# ES_Daisy_Pod_Rev5.net
KiCad netlist of a schematic drawn in EAGLE
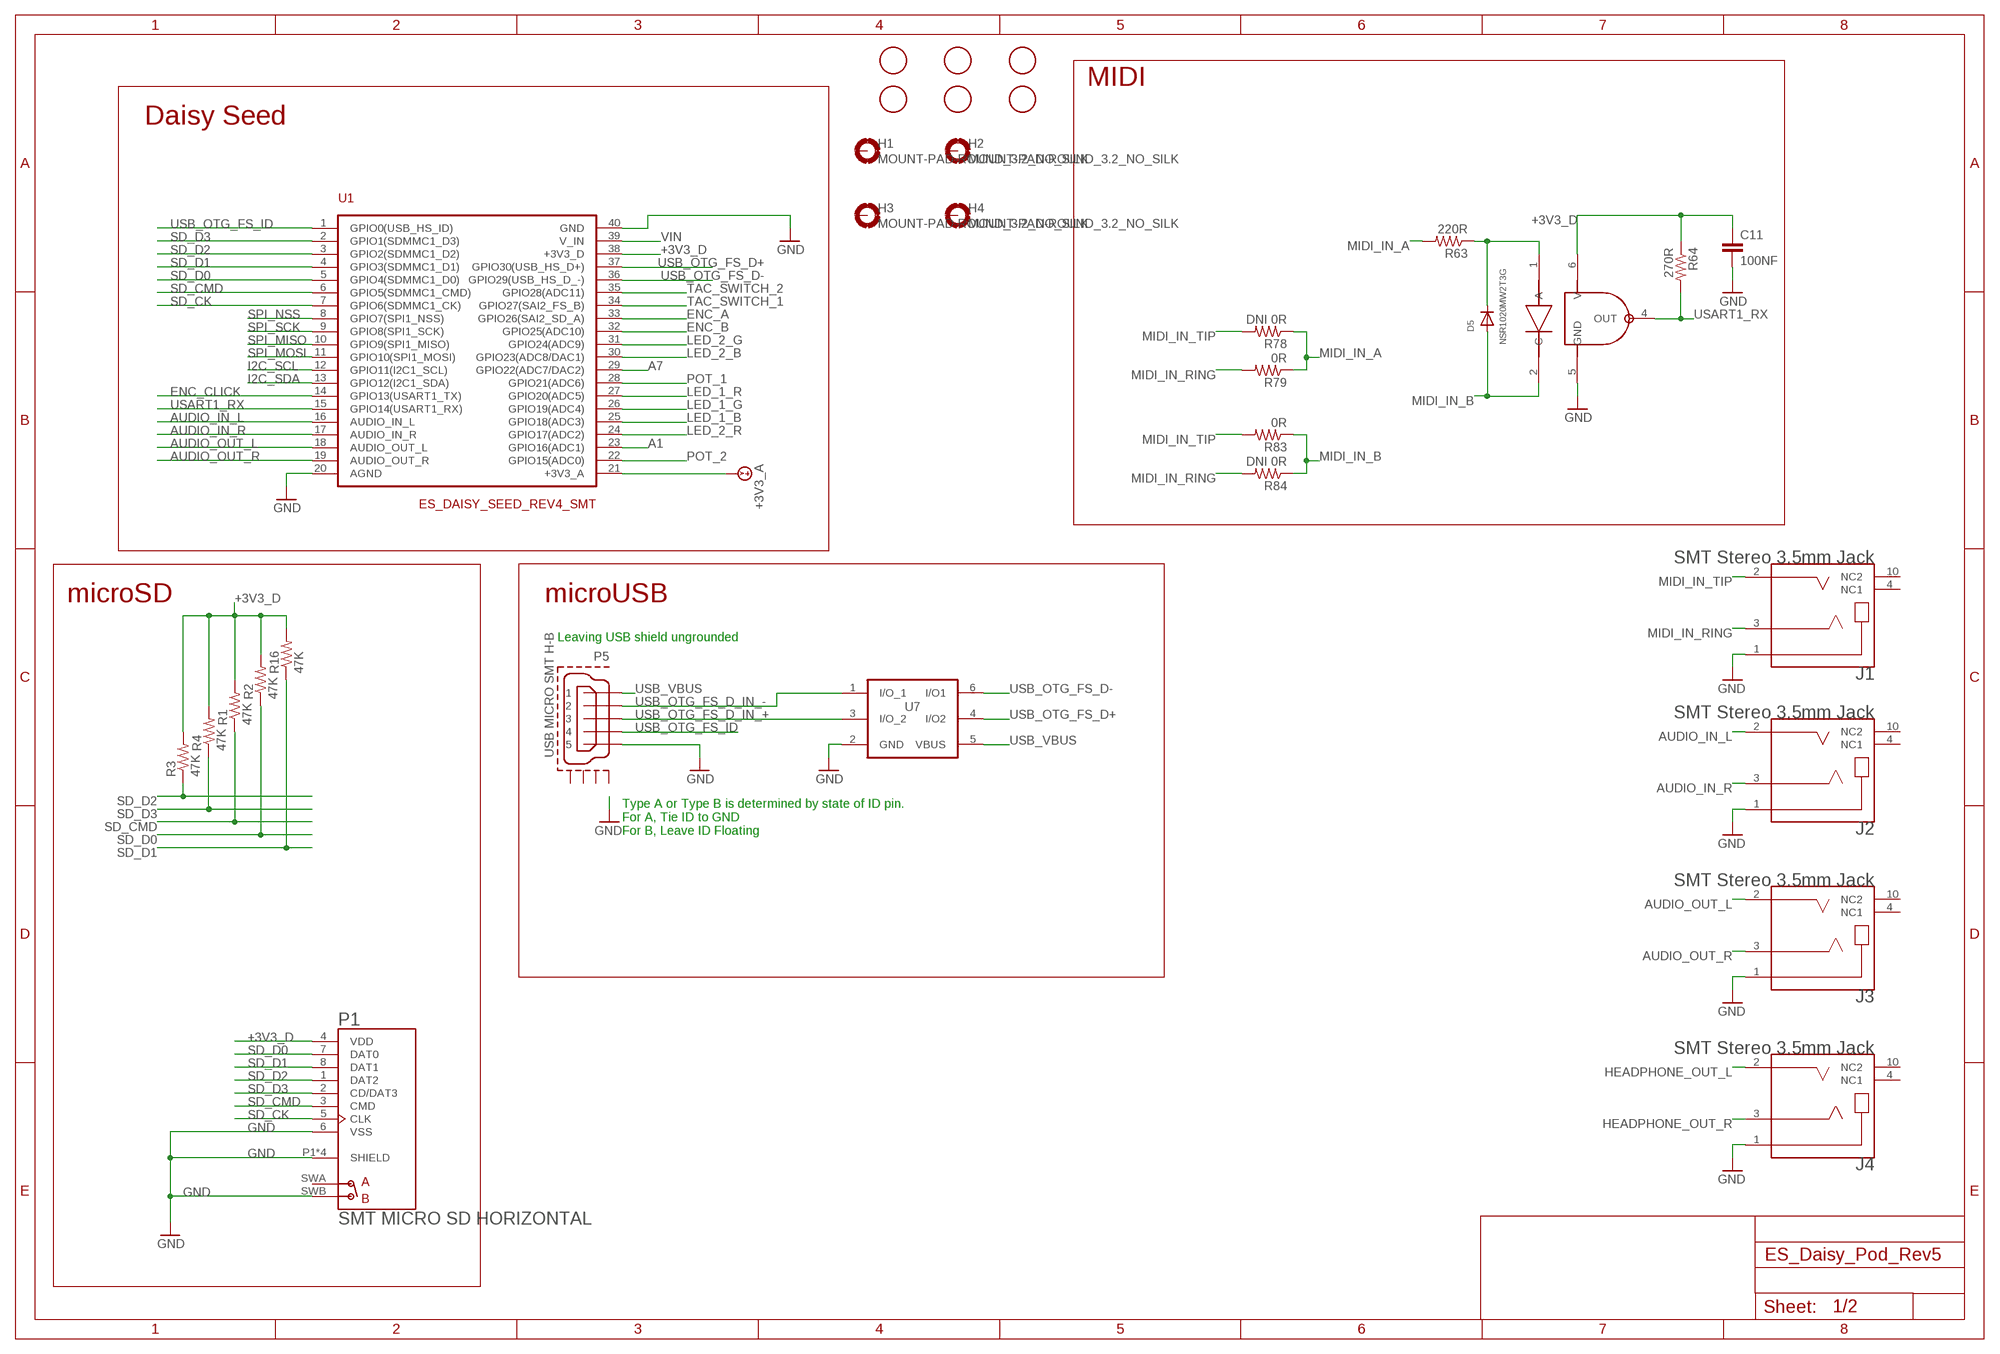
[diagram p0: schematic, sheet 1]
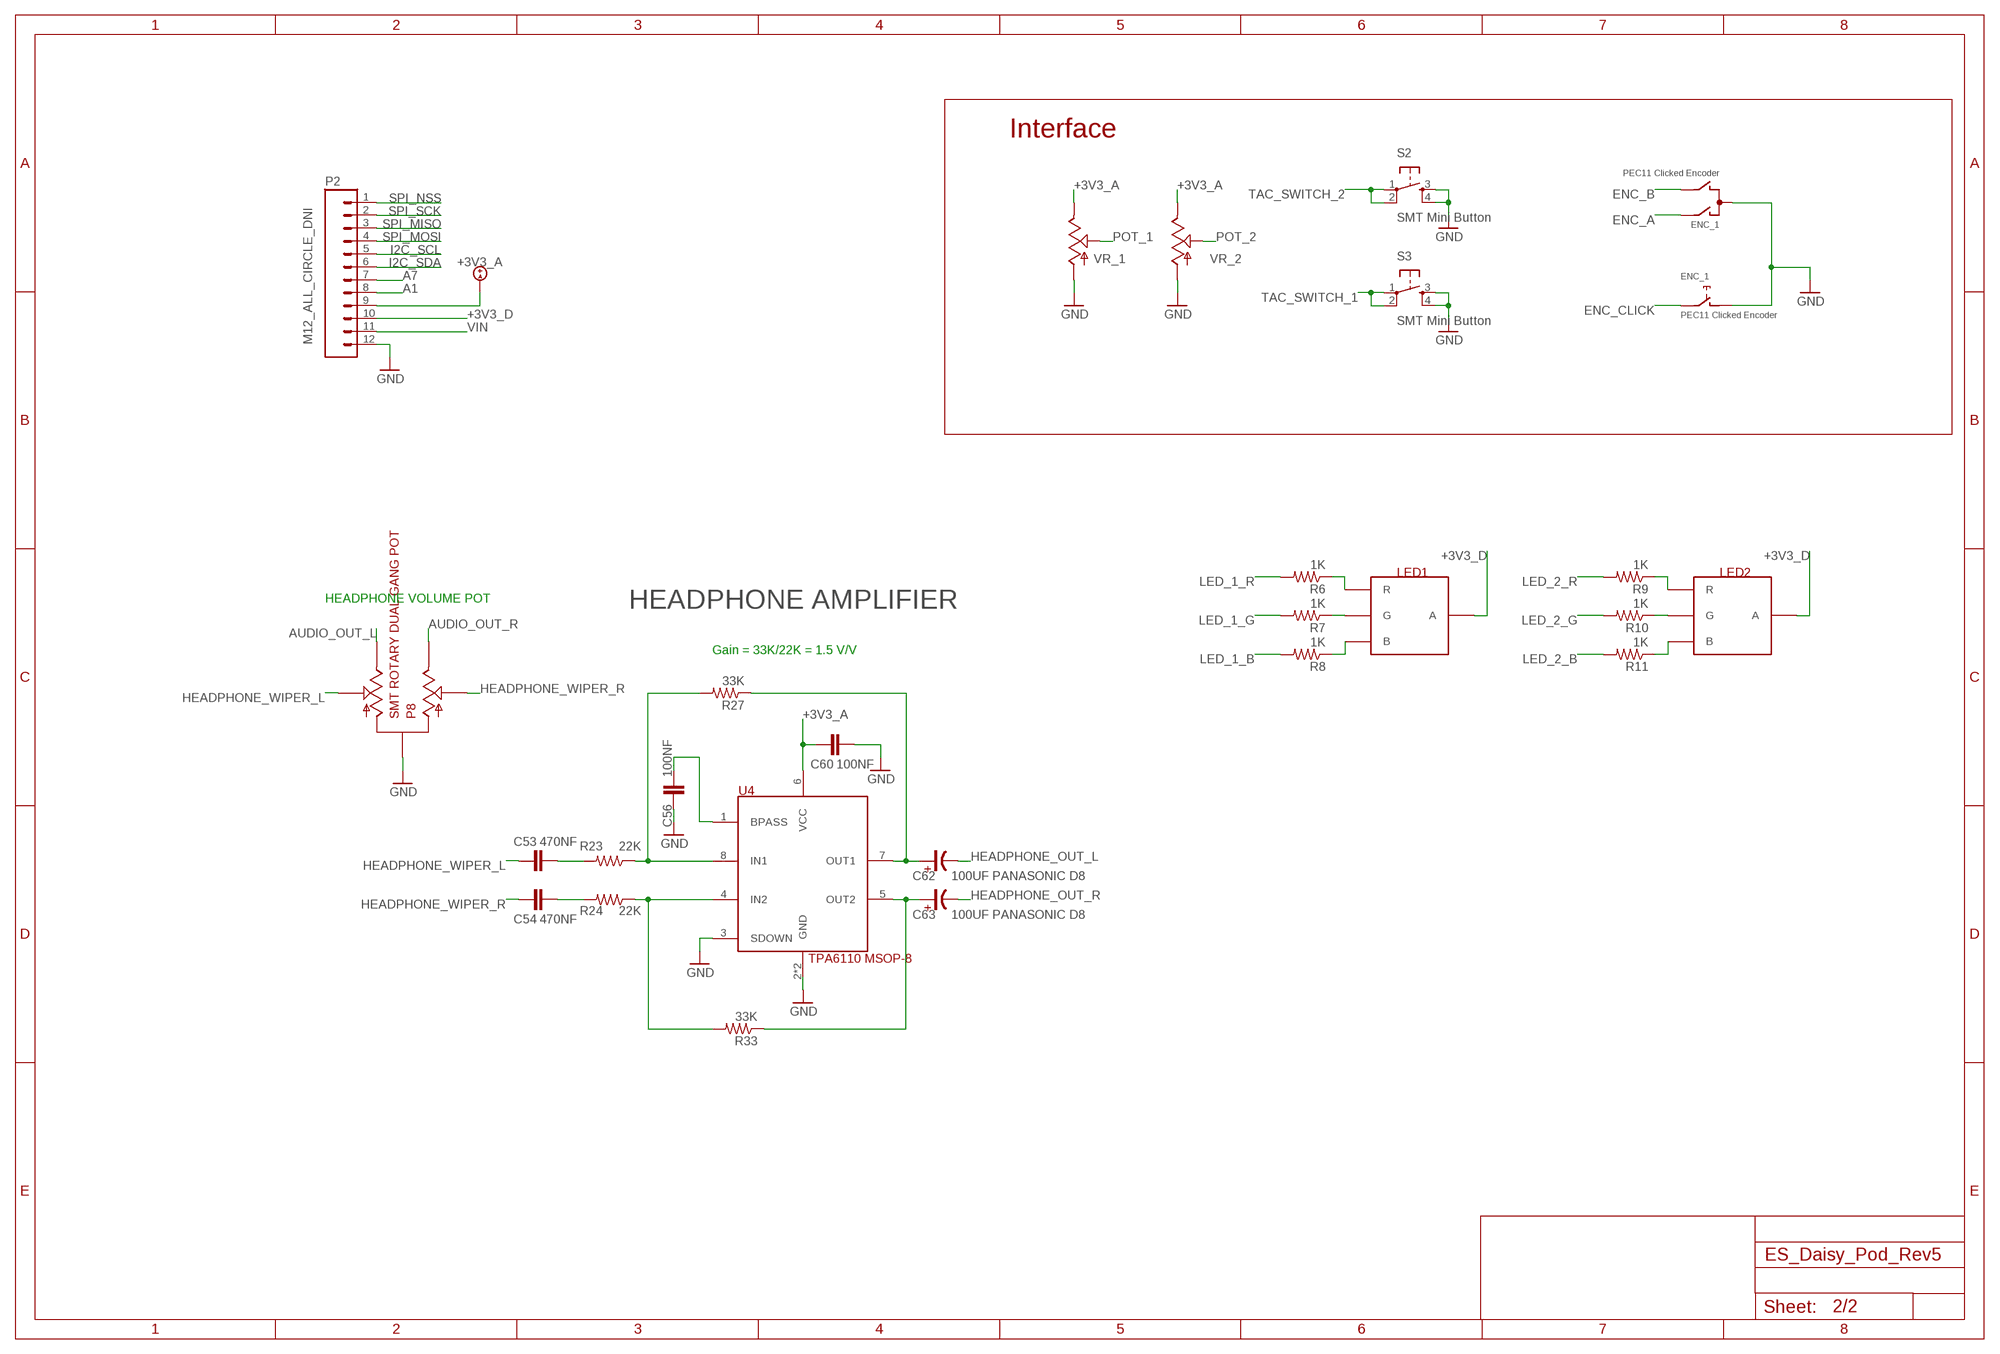
[diagram p1: schematic, sheet 2]

(export (version "E")
  (design (tool "Eeschema 10.0.6"))
  (components
    (comp (ref "C53")
      (value "470NF")
      (footprint "eagle-import:C0603")
      (libsource (lib "eagle-import") (part "C-EUC0603"))
    )
    (comp (ref "C54")
      (value "470NF")
      (footprint "eagle-import:C0603")
      (libsource (lib "eagle-import") (part "C-EUC0603"))
    )
    (comp (ref "C56")
      (value "100NF")
      (footprint "eagle-import:C0402")
      (libsource (lib "eagle-import") (part "C-EUC0402"))
    )
    (comp (ref "C60")
      (value "100NF")
      (footprint "eagle-import:C0402")
      (libsource (lib "eagle-import") (part "C-EUC0402"))
    )
    (comp (ref "C62")
      (value "100UF PANASONIC D8")
      (footprint "eagle-import:PANASONIC_D")
      (libsource (lib "eagle-import") (part "C-EU-POL_D"))
    )
    (comp (ref "C63")
      (value "100UF PANASONIC D8")
      (footprint "eagle-import:PANASONIC_D")
      (libsource (lib "eagle-import") (part "C-EU-POL_D"))
    )
    (comp (ref "ENC_1")
      (value "PEC11 Clicked Encoder")
      (footprint "eagle-import:VH1-147")
      (libsource (lib "eagle-import") (part "ENCODER_SMT"))
    )
    (comp (ref "LED1")
      (value "RGB LED SMT PLCC4")
      (footprint "eagle-import:P-LCC-4-3")
      (fields (field (name "MPN") "CLVBA-FKA-CC1F1L1BB7R3R3"))
      (libsource (lib "eagle-import") (part "LED_RGB_SMT"))
    )
    (comp (ref "LED2")
      (value "RGB LED SMT PLCC4")
      (footprint "eagle-import:P-LCC-4-3")
      (fields (field (name "MPN") "CLVBA-FKA-CC1F1L1BB7R3R3"))
      (libsource (lib "eagle-import") (part "LED_RGB_SMT"))
    )
    (comp (ref "P2")
      (value "M12_ALL_CIRCLE_DNI")
      (footprint "eagle-import:1X12_NO_SILK_ALL_CIRCLE")
      (libsource (lib "eagle-import") (part "M12_ALL_CIRCLE"))
    )
    (comp (ref "P8")
      (value "SMT ROTARY DUAL GANG POT")
      (footprint "eagle-import:RK10J12R0A0B")
      (libsource (lib "eagle-import") (part "ROTARY_POT"))
    )
    (comp (ref "R6")
      (value "1K")
      (footprint "eagle-import:R0402")
      (libsource (lib "eagle-import") (part "R-US_R0402"))
    )
    (comp (ref "R7")
      (value "1K")
      (footprint "eagle-import:R0402")
      (libsource (lib "eagle-import") (part "R-US_R0402"))
    )
    (comp (ref "R8")
      (value "1K")
      (footprint "eagle-import:R0402")
      (libsource (lib "eagle-import") (part "R-US_R0402"))
    )
    (comp (ref "R9")
      (value "1K")
      (footprint "eagle-import:R0402")
      (libsource (lib "eagle-import") (part "R-US_R0402"))
    )
    (comp (ref "R10")
      (value "1K")
      (footprint "eagle-import:R0402")
      (libsource (lib "eagle-import") (part "R-US_R0402"))
    )
    (comp (ref "R11")
      (value "1K")
      (footprint "eagle-import:R0402")
      (libsource (lib "eagle-import") (part "R-US_R0402"))
    )
    (comp (ref "R23")
      (value "22K")
      (footprint "eagle-import:R0603")
      (libsource (lib "eagle-import") (part "R-US_R0603"))
    )
    (comp (ref "R24")
      (value "22K")
      (footprint "eagle-import:R0603")
      (libsource (lib "eagle-import") (part "R-US_R0603"))
    )
    (comp (ref "R27")
      (value "33K")
      (footprint "eagle-import:R0603")
      (libsource (lib "eagle-import") (part "R-US_R0603"))
    )
    (comp (ref "R33")
      (value "33K")
      (footprint "eagle-import:R0603")
      (libsource (lib "eagle-import") (part "R-US_R0603"))
    )
    (comp (ref "S2")
      (value "SMT Mini Button")
      (footprint "eagle-import:TL3301SPF160QJ")
      (fields (field (name "MPN") "TL3301SPF160QJ"))
      (libsource (lib "eagle-import") (part "TAC_SWITCH_SMT"))
    )
    (comp (ref "S3")
      (value "SMT Mini Button")
      (footprint "eagle-import:TL3301SPF160QJ")
      (fields (field (name "MPN") "TL3301SPF160QJ"))
      (libsource (lib "eagle-import") (part "TAC_SWITCH_SMT"))
    )
    (comp (ref "U4")
      (value "TPA6110 MSOP-8")
      (footprint "eagle-import:MSOP_8_PWRPAD")
      (libsource (lib "eagle-import") (part "TPA6110MSOP"))
    )
    (comp (ref "VR_1")
      (value "P-10K-B-R-PIP")
      (footprint "eagle-import:9MM_SNAP-IN_POT_SILK_PIP")
      (libsource (lib "eagle-import") (part "POT_9MM_SNAP-IN__SILK_PIP"))
    )
    (comp (ref "VR_2")
      (value "P-10K-B-R-PIP")
      (footprint "eagle-import:9MM_SNAP-IN_POT_SILK_PIP")
      (libsource (lib "eagle-import") (part "POT_9MM_SNAP-IN__SILK_PIP"))
    )
    (comp (ref "C11")
      (value "100NF")
      (footprint "eagle-import:C0402")
      (libsource (lib "eagle-import") (part "C-EUC0402"))
    )
    (comp (ref "D5")
      (value "NSR1020MW2T3G")
      (footprint "eagle-import:SOD-323F")
      (libsource (lib "eagle-import") (part "DIODE_SOD-323F"))
    )
    (comp (ref "FD1")
      (value "FIDUCIAL")
      (footprint "eagle-import:FIDUCIAL_1MM")
      (libsource (lib "eagle-import") (part "FIDUCIAL"))
    )
    (comp (ref "FD2")
      (value "FIDUCIAL")
      (footprint "eagle-import:FIDUCIAL_1MM")
      (libsource (lib "eagle-import") (part "FIDUCIAL"))
    )
    (comp (ref "FD3")
      (value "FIDUCIAL")
      (footprint "eagle-import:FIDUCIAL_1MM")
      (libsource (lib "eagle-import") (part "FIDUCIAL"))
    )
    (comp (ref "FD4")
      (value "FIDUCIAL")
      (footprint "eagle-import:FIDUCIAL_1MM")
      (libsource (lib "eagle-import") (part "FIDUCIAL"))
    )
    (comp (ref "FD5")
      (value "FIDUCIAL")
      (footprint "eagle-import:FIDUCIAL_1MM")
      (libsource (lib "eagle-import") (part "FIDUCIAL"))
    )
    (comp (ref "FD6")
      (value "FIDUCIAL")
      (footprint "eagle-import:FIDUCIAL_1MM")
      (libsource (lib "eagle-import") (part "FIDUCIAL"))
    )
    (comp (ref "H1")
      (value "MOUNT-PAD-ROUND_3.2_NO_SILK")
      (footprint "eagle-import:32-PAD_NO_SILK")
      (libsource (lib "eagle-import") (part "MOUNT-PAD-ROUND_3.2_NO_SILK"))
    )
    (comp (ref "H2")
      (value "MOUNT-PAD-ROUND_3.2_NO_SILK")
      (footprint "eagle-import:32-PAD_NO_SILK")
      (libsource (lib "eagle-import") (part "MOUNT-PAD-ROUND_3.2_NO_SILK"))
    )
    (comp (ref "H3")
      (value "MOUNT-PAD-ROUND_3.2_NO_SILK")
      (footprint "eagle-import:32-PAD_NO_SILK")
      (libsource (lib "eagle-import") (part "MOUNT-PAD-ROUND_3.2_NO_SILK"))
    )
    (comp (ref "H4")
      (value "MOUNT-PAD-ROUND_3.2_NO_SILK")
      (footprint "eagle-import:32-PAD_NO_SILK")
      (libsource (lib "eagle-import") (part "MOUNT-PAD-ROUND_3.2_NO_SILK"))
    )
    (comp (ref "J1")
      (value "SMT Stereo 3.5mm Jack")
      (footprint "eagle-import:CUI_SJ2-35863B1-SMT-TR")
      (fields (field (name "MF") "CUI Inc.") (field (name "MP") "SJ2-35863B1-SMT-TR"))
      (libsource (lib "eagle-import") (part "SJ2_TRS_JACK"))
    )
    (comp (ref "J2")
      (value "SMT Stereo 3.5mm Jack")
      (footprint "eagle-import:CUI_SJ2-35863B1-SMT-TR")
      (fields (field (name "MF") "CUI Inc.") (field (name "MP") "SJ2-35863B1-SMT-TR"))
      (libsource (lib "eagle-import") (part "SJ2_TRS_JACK"))
    )
    (comp (ref "J3")
      (value "SMT Stereo 3.5mm Jack")
      (footprint "eagle-import:CUI_SJ2-35863B1-SMT-TR")
      (fields (field (name "MF") "CUI Inc.") (field (name "MP") "SJ2-35863B1-SMT-TR"))
      (libsource (lib "eagle-import") (part "SJ2_TRS_JACK"))
    )
    (comp (ref "J4")
      (value "SMT Stereo 3.5mm Jack")
      (footprint "eagle-import:CUI_SJ2-35863B1-SMT-TR")
      (fields (field (name "MF") "CUI Inc.") (field (name "MP") "SJ2-35863B1-SMT-TR"))
      (libsource (lib "eagle-import") (part "SJ2_TRS_JACK"))
    )
    (comp (ref "P1")
      (value "SMT MICRO SD HORIZONTAL")
      (footprint "eagle-import:HRS_DM3AT-SF-PEJM5")
      (fields (field (name "MF") "Hirose") (field (name "MP") "DM3AT-SF-PEJM5"))
      (libsource (lib "eagle-import") (part "MICRO_SD_RIGHT_ANGLE"))
    )
    (comp (ref "P5")
      (value "USB MICRO SMT H-B")
      (footprint "eagle-import:47589-0001_CUT2")
      (libsource (lib "eagle-import") (part "USB_MICRO_AB_CUT2"))
    )
    (comp (ref "R1")
      (value "47K")
      (footprint "eagle-import:R0603")
      (libsource (lib "eagle-import") (part "R-US_R0603"))
    )
    (comp (ref "R2")
      (value "47K")
      (footprint "eagle-import:R0603")
      (libsource (lib "eagle-import") (part "R-US_R0603"))
    )
    (comp (ref "R3")
      (value "47K")
      (footprint "eagle-import:R0603")
      (libsource (lib "eagle-import") (part "R-US_R0603"))
    )
    (comp (ref "R4")
      (value "47K")
      (footprint "eagle-import:R0603")
      (libsource (lib "eagle-import") (part "R-US_R0603"))
    )
    (comp (ref "R16")
      (value "47K")
      (footprint "eagle-import:R0603")
      (libsource (lib "eagle-import") (part "R-US_R0603"))
    )
    (comp (ref "R63")
      (value "220R")
      (footprint "eagle-import:R0603")
      (libsource (lib "eagle-import") (part "R-US_R0603"))
    )
    (comp (ref "R64")
      (value "270R")
      (footprint "eagle-import:R0603")
      (libsource (lib "eagle-import") (part "R-US_R0603"))
    )
    (comp (ref "R78")
      (value "DNI 0R")
      (footprint "eagle-import:R0603")
      (libsource (lib "eagle-import") (part "R-US_R0603"))
    )
    (comp (ref "R79")
      (value "0R")
      (footprint "eagle-import:R0603")
      (libsource (lib "eagle-import") (part "R-US_R0603"))
    )
    (comp (ref "R83")
      (value "0R")
      (footprint "eagle-import:R0603")
      (libsource (lib "eagle-import") (part "R-US_R0603"))
    )
    (comp (ref "R84")
      (value "DNI 0R")
      (footprint "eagle-import:R0603")
      (libsource (lib "eagle-import") (part "R-US_R0603"))
    )
    (comp (ref "U1")
      (value "ES_DAISY_SEED_REV4_SMT")
      (footprint "eagle-import:ES_DAISY_SEED_SMT")
      (libsource (lib "eagle-import") (part "ES_DAISY_SEED_REV4_SMT"))
    )
    (comp (ref "U7")
      (value "USBLC6 TVS SOT-23-6")
      (footprint "eagle-import:SOT-23-6L")
      (fields (field (name "MPN") "USBLC6-2SC6"))
      (libsource (lib "eagle-import") (part "USBLC6-2SC6"))
    )
    (comp (ref "U15")
      (value "H11L1SR2M")
      (footprint "eagle-import:DIL06_GULLWING")
      (libsource (lib "eagle-import") (part "OPTOISOLATOR_H11L1M"))
    )
  )
  (nets
    (net (code "1") (name "+3V3_A") (class "Default")
      (node (ref "C60") (pin "2") (pinfunction "2_2") (pintype "passive"))
      (node (ref "P2") (pin "9") (pinfunction "9_9") (pintype "passive"))
      (node (ref "U1") (pin "21") (pinfunction "+3V3_A_21") (pintype "bidirectional"))
      (node (ref "U4") (pin "6") (pinfunction "VCC_6") (pintype "bidirectional"))
      (node (ref "VR_1") (pin "3") (pinfunction "3_3") (pintype "passive"))
      (node (ref "VR_2") (pin "3") (pinfunction "3_3") (pintype "passive"))
    )
    (net (code "2") (name "+3V3_D") (class "Default")
      (node (ref "C11") (pin "1") (pinfunction "1_1") (pintype "passive"))
      (node (ref "LED1") (pin "2") (pinfunction "A_2") (pintype "bidirectional"))
      (node (ref "LED2") (pin "2") (pinfunction "A_2") (pintype "bidirectional"))
      (node (ref "P1") (pin "4") (pinfunction "VDD_4") (pintype "power_in"))
      (node (ref "P2") (pin "10") (pinfunction "10_10") (pintype "passive"))
      (node (ref "R1") (pin "2") (pinfunction "2_2") (pintype "passive"))
      (node (ref "R16") (pin "2") (pinfunction "2_2") (pintype "passive"))
      (node (ref "R2") (pin "2") (pinfunction "2_2") (pintype "passive"))
      (node (ref "R3") (pin "2") (pinfunction "2_2") (pintype "passive"))
      (node (ref "R4") (pin "2") (pinfunction "2_2") (pintype "passive"))
      (node (ref "R64") (pin "1") (pinfunction "1_1") (pintype "passive"))
      (node (ref "U1") (pin "38") (pinfunction "+3V3_D_38") (pintype "bidirectional"))
      (node (ref "U15") (pin "6") (pinfunction "V_6") (pintype "bidirectional"))
    )
    (net (code "3") (name "A1") (class "Default")
      (node (ref "P2") (pin "8") (pinfunction "8_8") (pintype "passive"))
      (node (ref "U1") (pin "23") (pinfunction "GPIO16(ADC1)_23") (pintype "bidirectional"))
    )
    (net (code "4") (name "A7") (class "Default")
      (node (ref "P2") (pin "7") (pinfunction "7_7") (pintype "passive"))
      (node (ref "U1") (pin "29") (pinfunction "GPIO22(ADC7/DAC2)_29") (pintype "bidirectional"))
    )
    (net (code "5") (name "AUDIO_IN_L") (class "Default")
      (node (ref "J2") (pin "2") (pinfunction "TIP_2") (pintype "passive"))
      (node (ref "U1") (pin "16") (pinfunction "AUDIO_IN_L_16") (pintype "bidirectional"))
    )
    (net (code "6") (name "AUDIO_IN_R") (class "Default")
      (node (ref "J2") (pin "3") (pinfunction "RING_3") (pintype "passive"))
      (node (ref "U1") (pin "17") (pinfunction "AUDIO_IN_R_17") (pintype "bidirectional"))
    )
    (net (code "7") (name "AUDIO_OUT_L") (class "Default")
      (node (ref "J3") (pin "2") (pinfunction "TIP_2") (pintype "passive"))
      (node (ref "P8") (pin "P$5") (pinfunction "P$5_P$5") (pintype "bidirectional"))
      (node (ref "U1") (pin "18") (pinfunction "AUDIO_OUT_L_18") (pintype "bidirectional"))
    )
    (net (code "8") (name "AUDIO_OUT_R") (class "Default")
      (node (ref "J3") (pin "3") (pinfunction "RING_3") (pintype "passive"))
      (node (ref "P8") (pin "P$4") (pinfunction "P$4_P$4") (pintype "bidirectional"))
      (node (ref "U1") (pin "19") (pinfunction "AUDIO_OUT_R_19") (pintype "bidirectional"))
    )
    (net (code "9") (name "ENC_A") (class "Default")
      (node (ref "ENC_1") (pin "A") (pinfunction "A_A") (pintype "passive"))
      (node (ref "U1") (pin "33") (pinfunction "GPIO26(SAI2_SD_A)_33") (pintype "bidirectional"))
    )
    (net (code "10") (name "ENC_B") (class "Default")
      (node (ref "ENC_1") (pin "B") (pinfunction "B_B") (pintype "passive"))
      (node (ref "U1") (pin "32") (pinfunction "GPIO25(ADC10)_32") (pintype "bidirectional"))
    )
    (net (code "11") (name "ENC_CLICK") (class "Default")
      (node (ref "ENC_1") (pin "E") (pinfunction "2_E") (pintype "passive"))
      (node (ref "U1") (pin "14") (pinfunction "GPIO13(USART1_TX)_14") (pintype "bidirectional"))
    )
    (net (code "12") (name "GND") (class "Default")
      (node (ref "C11") (pin "2") (pinfunction "2_2") (pintype "passive"))
      (node (ref "C56") (pin "1") (pinfunction "1_1") (pintype "passive"))
      (node (ref "C60") (pin "1") (pinfunction "1_1") (pintype "passive"))
      (node (ref "ENC_1") (pin "C") (pinfunction "C_C") (pintype "passive"))
      (node (ref "ENC_1") (pin "D") (pinfunction "1_D") (pintype "passive"))
      (node (ref "J1") (pin "1") (pinfunction "SLEEVE_1") (pintype "passive"))
      (node (ref "J2") (pin "1") (pinfunction "SLEEVE_1") (pintype "passive"))
      (node (ref "J3") (pin "1") (pinfunction "SLEEVE_1") (pintype "passive"))
      (node (ref "J4") (pin "1") (pinfunction "SLEEVE_1") (pintype "passive"))
      (node (ref "P1") (pin "6") (pinfunction "VSS_6") (pintype "power_in"))
      (node (ref "P1") (pin "P1") (pinfunction "SHIELD_P1") (pintype "passive"))
      (node (ref "P1") (pin "P2") (pinfunction "SHIELD_P2") (pintype "passive"))
      (node (ref "P1") (pin "P3") (pinfunction "SHIELD_P3") (pintype "passive"))
      (node (ref "P1") (pin "P4") (pinfunction "SHIELD_P4") (pintype "passive"))
      (node (ref "P1") (pin "SWB") (pinfunction "B_SWB") (pintype "bidirectional"))
      (node (ref "P2") (pin "12") (pinfunction "12_12") (pintype "passive"))
      (node (ref "P5") (pin "5") (pinfunction "5_5") (pintype "input"))
      (node (ref "P8") (pin "P$1") (pinfunction "P$1_P$1") (pintype "bidirectional"))
      (node (ref "S2") (pin "3") (pinfunction "3_3") (pintype "passive"))
      (node (ref "S2") (pin "4") (pinfunction "4_4") (pintype "passive"))
      (node (ref "S3") (pin "3") (pinfunction "3_3") (pintype "passive"))
      (node (ref "S3") (pin "4") (pinfunction "4_4") (pintype "passive"))
      (node (ref "U1") (pin "20") (pinfunction "AGND_20") (pintype "bidirectional"))
      (node (ref "U1") (pin "40") (pinfunction "GND_40") (pintype "bidirectional"))
      (node (ref "U15") (pin "5") (pinfunction "GND_5") (pintype "bidirectional"))
      (node (ref "U4") (pin "2") (pinfunction "GND_2") (pintype "bidirectional"))
      (node (ref "U4") (pin "3") (pinfunction "SDOWN_3") (pintype "bidirectional"))
      (node (ref "U4") (pin "9") (pinfunction "GND_9") (pintype "bidirectional"))
      (node (ref "U7") (pin "2") (pinfunction "GND_2") (pintype "bidirectional"))
      (node (ref "VR_1") (pin "1") (pinfunction "1_1") (pintype "passive"))
      (node (ref "VR_2") (pin "1") (pinfunction "1_1") (pintype "passive"))
    )
    (net (code "13") (name "HEADPHONE_OUT_L") (class "Default")
      (node (ref "C62") (pin "-") (pinfunction "NEG_-") (pintype "passive"))
      (node (ref "J4") (pin "2") (pinfunction "TIP_2") (pintype "passive"))
    )
    (net (code "14") (name "HEADPHONE_OUT_R") (class "Default")
      (node (ref "C63") (pin "-") (pinfunction "NEG_-") (pintype "passive"))
      (node (ref "J4") (pin "3") (pinfunction "RING_3") (pintype "passive"))
    )
    (net (code "15") (name "HEADPHONE_WIPER_L") (class "Default")
      (node (ref "C53") (pin "1") (pinfunction "1_1") (pintype "passive"))
      (node (ref "P8") (pin "P$2") (pinfunction "P$2_P$2") (pintype "bidirectional"))
    )
    (net (code "16") (name "HEADPHONE_WIPER_R") (class "Default")
      (node (ref "C54") (pin "1") (pinfunction "1_1") (pintype "passive"))
      (node (ref "P8") (pin "P$3") (pinfunction "P$3_P$3") (pintype "bidirectional"))
    )
    (net (code "17") (name "I2C_SCL") (class "Default")
      (node (ref "P2") (pin "5") (pinfunction "5_5") (pintype "passive"))
      (node (ref "U1") (pin "12") (pinfunction "GPIO11(I2C1_SCL)_12") (pintype "bidirectional"))
    )
    (net (code "18") (name "I2C_SDA") (class "Default")
      (node (ref "P2") (pin "6") (pinfunction "6_6") (pintype "passive"))
      (node (ref "U1") (pin "13") (pinfunction "GPIO12(I2C1_SDA)_13") (pintype "bidirectional"))
    )
    (net (code "19") (name "LED_1_B") (class "Default")
      (node (ref "R8") (pin "2") (pinfunction "2_2") (pintype "passive"))
      (node (ref "U1") (pin "25") (pinfunction "GPIO18(ADC3)_25") (pintype "bidirectional"))
    )
    (net (code "20") (name "LED_1_G") (class "Default")
      (node (ref "R7") (pin "2") (pinfunction "2_2") (pintype "passive"))
      (node (ref "U1") (pin "26") (pinfunction "GPIO19(ADC4)_26") (pintype "bidirectional"))
    )
    (net (code "21") (name "LED_1_R") (class "Default")
      (node (ref "R6") (pin "2") (pinfunction "2_2") (pintype "passive"))
      (node (ref "U1") (pin "27") (pinfunction "GPIO20(ADC5)_27") (pintype "bidirectional"))
    )
    (net (code "22") (name "LED_2_B") (class "Default")
      (node (ref "R11") (pin "2") (pinfunction "2_2") (pintype "passive"))
      (node (ref "U1") (pin "30") (pinfunction "GPIO23(ADC8/DAC1)_30") (pintype "bidirectional"))
    )
    (net (code "23") (name "LED_2_G") (class "Default")
      (node (ref "R10") (pin "2") (pinfunction "2_2") (pintype "passive"))
      (node (ref "U1") (pin "31") (pinfunction "GPIO24(ADC9)_31") (pintype "bidirectional"))
    )
    (net (code "24") (name "LED_2_R") (class "Default")
      (node (ref "R9") (pin "2") (pinfunction "2_2") (pintype "passive"))
      (node (ref "U1") (pin "24") (pinfunction "GPIO17(ADC2)_24") (pintype "bidirectional"))
    )
    (net (code "25") (name "MIDI_IN_A") (class "Default")
      (node (ref "R63") (pin "2") (pinfunction "2_2") (pintype "passive"))
      (node (ref "R78") (pin "1") (pinfunction "1_1") (pintype "passive"))
      (node (ref "R79") (pin "1") (pinfunction "1_1") (pintype "passive"))
    )
    (net (code "26") (name "MIDI_IN_B") (class "Default")
      (node (ref "D5") (pin "A") (pinfunction "A_A") (pintype "passive"))
      (node (ref "R83") (pin "1") (pinfunction "1_1") (pintype "passive"))
      (node (ref "R84") (pin "1") (pinfunction "1_1") (pintype "passive"))
      (node (ref "U15") (pin "2") (pinfunction "C_2") (pintype "bidirectional"))
    )
    (net (code "27") (name "MIDI_IN_RING") (class "Default")
      (node (ref "J1") (pin "3") (pinfunction "RING_3") (pintype "passive"))
      (node (ref "R79") (pin "2") (pinfunction "2_2") (pintype "passive"))
      (node (ref "R84") (pin "2") (pinfunction "2_2") (pintype "passive"))
    )
    (net (code "28") (name "MIDI_IN_TIP") (class "Default")
      (node (ref "J1") (pin "2") (pinfunction "TIP_2") (pintype "passive"))
      (node (ref "R78") (pin "2") (pinfunction "2_2") (pintype "passive"))
      (node (ref "R83") (pin "2") (pinfunction "2_2") (pintype "passive"))
    )
    (net (code "29") (name "Net-(C53-Pad2)") (class "Default")
      (node (ref "C53") (pin "2") (pinfunction "2_2") (pintype "passive"))
      (node (ref "R23") (pin "2") (pinfunction "2_2") (pintype "passive"))
    )
    (net (code "30") (name "Net-(C54-Pad2)") (class "Default")
      (node (ref "C54") (pin "2") (pinfunction "2_2") (pintype "passive"))
      (node (ref "R24") (pin "2") (pinfunction "2_2") (pintype "passive"))
    )
    (net (code "31") (name "Net-(C62-POS)") (class "Default")
      (node (ref "C62") (pin "+") (pinfunction "POS_+") (pintype "passive"))
      (node (ref "R27") (pin "1") (pinfunction "1_1") (pintype "passive"))
      (node (ref "U4") (pin "7") (pinfunction "OUT1_7") (pintype "bidirectional"))
    )
    (net (code "32") (name "Net-(C63-POS)") (class "Default")
      (node (ref "C63") (pin "+") (pinfunction "POS_+") (pintype "passive"))
      (node (ref "R33") (pin "1") (pinfunction "1_1") (pintype "passive"))
      (node (ref "U4") (pin "5") (pinfunction "OUT2_5") (pintype "bidirectional"))
    )
    (net (code "33") (name "Net-(LED1-B)") (class "Default")
      (node (ref "LED1") (pin "3") (pinfunction "B_3") (pintype "bidirectional"))
      (node (ref "R8") (pin "1") (pinfunction "1_1") (pintype "passive"))
    )
    (net (code "34") (name "Net-(LED1-G)") (class "Default")
      (node (ref "LED1") (pin "4") (pinfunction "G_4") (pintype "bidirectional"))
      (node (ref "R7") (pin "1") (pinfunction "1_1") (pintype "passive"))
    )
    (net (code "35") (name "Net-(LED1-R)") (class "Default")
      (node (ref "LED1") (pin "1") (pinfunction "R_1") (pintype "bidirectional"))
      (node (ref "R6") (pin "1") (pinfunction "1_1") (pintype "passive"))
    )
    (net (code "36") (name "Net-(LED2-B)") (class "Default")
      (node (ref "LED2") (pin "3") (pinfunction "B_3") (pintype "bidirectional"))
      (node (ref "R11") (pin "1") (pinfunction "1_1") (pintype "passive"))
    )
    (net (code "37") (name "Net-(LED2-G)") (class "Default")
      (node (ref "LED2") (pin "4") (pinfunction "G_4") (pintype "bidirectional"))
      (node (ref "R10") (pin "1") (pinfunction "1_1") (pintype "passive"))
    )
    (net (code "38") (name "Net-(LED2-R)") (class "Default")
      (node (ref "LED2") (pin "1") (pinfunction "R_1") (pintype "bidirectional"))
      (node (ref "R9") (pin "1") (pinfunction "1_1") (pintype "passive"))
    )
    (net (code "39") (name "Net-(U4-BPASS)") (class "Default")
      (node (ref "C56") (pin "2") (pinfunction "2_2") (pintype "passive"))
      (node (ref "U4") (pin "1") (pinfunction "BPASS_1") (pintype "bidirectional"))
    )
    (net (code "40") (name "Net-(U4-IN1)") (class "Default")
      (node (ref "R23") (pin "1") (pinfunction "1_1") (pintype "passive"))
      (node (ref "R27") (pin "2") (pinfunction "2_2") (pintype "passive"))
      (node (ref "U4") (pin "8") (pinfunction "IN1_8") (pintype "bidirectional"))
    )
    (net (code "41") (name "Net-(U4-IN2)") (class "Default")
      (node (ref "R24") (pin "1") (pinfunction "1_1") (pintype "passive"))
      (node (ref "R33") (pin "2") (pinfunction "2_2") (pintype "passive"))
      (node (ref "U4") (pin "4") (pinfunction "IN2_4") (pintype "bidirectional"))
    )
    (net (code "42") (name "Net-(U15-A)") (class "Default")
      (node (ref "D5") (pin "C") (pinfunction "C_C") (pintype "passive"))
      (node (ref "R63") (pin "1") (pinfunction "1_1") (pintype "passive"))
      (node (ref "U15") (pin "1") (pinfunction "A_1") (pintype "bidirectional"))
    )
    (net (code "43") (name "POT_1") (class "Default")
      (node (ref "U1") (pin "28") (pinfunction "GPIO21(ADC6)_28") (pintype "bidirectional"))
      (node (ref "VR_1") (pin "2") (pinfunction "2_2") (pintype "passive"))
    )
    (net (code "44") (name "POT_2") (class "Default")
      (node (ref "U1") (pin "22") (pinfunction "GPIO15(ADC0)_22") (pintype "bidirectional"))
      (node (ref "VR_2") (pin "2") (pinfunction "2_2") (pintype "passive"))
    )
    (net (code "45") (name "SD_CK") (class "Default")
      (node (ref "P1") (pin "5") (pinfunction "CLK_5") (pintype "bidirectional"))
      (node (ref "U1") (pin "7") (pinfunction "GPIO6(SDMMC1_CK)_7") (pintype "bidirectional"))
    )
    (net (code "46") (name "SD_CMD") (class "Default")
      (node (ref "P1") (pin "3") (pinfunction "CMD_3") (pintype "bidirectional"))
      (node (ref "R1") (pin "1") (pinfunction "1_1") (pintype "passive"))
      (node (ref "U1") (pin "6") (pinfunction "GPIO5(SDMMC1_CMD)_6") (pintype "bidirectional"))
    )
    (net (code "47") (name "SD_D0") (class "Default")
      (node (ref "P1") (pin "7") (pinfunction "DAT0_7") (pintype "bidirectional"))
      (node (ref "R2") (pin "1") (pinfunction "1_1") (pintype "passive"))
      (node (ref "U1") (pin "5") (pinfunction "GPIO4(SDMMC1_D0)_5") (pintype "bidirectional"))
    )
    (net (code "48") (name "SD_D1") (class "Default")
      (node (ref "P1") (pin "8") (pinfunction "DAT1_8") (pintype "bidirectional"))
      (node (ref "R16") (pin "1") (pinfunction "1_1") (pintype "passive"))
      (node (ref "U1") (pin "4") (pinfunction "GPIO3(SDMMC1_D1)_4") (pintype "bidirectional"))
    )
    (net (code "49") (name "SD_D2") (class "Default")
      (node (ref "P1") (pin "1") (pinfunction "DAT2_1") (pintype "bidirectional"))
      (node (ref "R3") (pin "1") (pinfunction "1_1") (pintype "passive"))
      (node (ref "U1") (pin "3") (pinfunction "GPIO2(SDMMC1_D2)_3") (pintype "bidirectional"))
    )
    (net (code "50") (name "SD_D3") (class "Default")
      (node (ref "P1") (pin "2") (pinfunction "CD/DAT3_2") (pintype "bidirectional"))
      (node (ref "R4") (pin "1") (pinfunction "1_1") (pintype "passive"))
      (node (ref "U1") (pin "2") (pinfunction "GPIO1(SDMMC1_D3)_2") (pintype "bidirectional"))
    )
    (net (code "51") (name "SPI_MISO") (class "Default")
      (node (ref "P2") (pin "3") (pinfunction "3_3") (pintype "passive"))
      (node (ref "U1") (pin "10") (pinfunction "GPIO9(SPI1_MISO)_10") (pintype "bidirectional"))
    )
    (net (code "52") (name "SPI_MOSI") (class "Default")
      (node (ref "P2") (pin "4") (pinfunction "4_4") (pintype "passive"))
      (node (ref "U1") (pin "11") (pinfunction "GPIO10(SPI1_MOSI)_11") (pintype "bidirectional"))
    )
    (net (code "53") (name "SPI_NSS") (class "Default")
      (node (ref "P2") (pin "1") (pinfunction "1_1") (pintype "passive"))
      (node (ref "U1") (pin "8") (pinfunction "GPIO7(SPI1_NSS)_8") (pintype "bidirectional"))
    )
    (net (code "54") (name "SPI_SCK") (class "Default")
      (node (ref "P2") (pin "2") (pinfunction "2_2") (pintype "passive"))
      (node (ref "U1") (pin "9") (pinfunction "GPIO8(SPI1_SCK)_9") (pintype "bidirectional"))
    )
    (net (code "55") (name "TAC_SWITCH_1") (class "Default")
      (node (ref "S3") (pin "1") (pinfunction "1_1") (pintype "passive"))
      (node (ref "S3") (pin "2") (pinfunction "2_2") (pintype "passive"))
      (node (ref "U1") (pin "34") (pinfunction "GPIO27(SAI2_FS_B)_34") (pintype "bidirectional"))
    )
    (net (code "56") (name "TAC_SWITCH_2") (class "Default")
      (node (ref "S2") (pin "1") (pinfunction "1_1") (pintype "passive"))
      (node (ref "S2") (pin "2") (pinfunction "2_2") (pintype "passive"))
      (node (ref "U1") (pin "35") (pinfunction "GPIO28(ADC11)_35") (pintype "bidirectional"))
    )
    (net (code "57") (name "USART1_RX") (class "Default")
      (node (ref "R64") (pin "2") (pinfunction "2_2") (pintype "passive"))
      (node (ref "U1") (pin "15") (pinfunction "GPIO14(USART1_RX)_15") (pintype "bidirectional"))
      (node (ref "U15") (pin "4") (pinfunction "OUT_4") (pintype "bidirectional"))
    )
    (net (code "58") (name "USB_OTG_FS_D+") (class "Default")
      (node (ref "U1") (pin "37") (pinfunction "GPIO30(USB_HS_D+)_37") (pintype "bidirectional"))
      (node (ref "U7") (pin "4") (pinfunction "I/O2_4") (pintype "bidirectional"))
    )
    (net (code "59") (name "USB_OTG_FS_D-") (class "Default")
      (node (ref "U1") (pin "36") (pinfunction "GPIO29(USB_HS_D_-)_36") (pintype "bidirectional"))
      (node (ref "U7") (pin "6") (pinfunction "I/O1_6") (pintype "bidirectional"))
    )
    (net (code "60") (name "USB_OTG_FS_D_IN_+") (class "Default")
      (node (ref "P5") (pin "3") (pinfunction "3_3") (pintype "input"))
      (node (ref "U7") (pin "3") (pinfunction "I/O_2_3") (pintype "bidirectional"))
    )
    (net (code "61") (name "USB_OTG_FS_D_IN_-") (class "Default")
      (node (ref "P5") (pin "2") (pinfunction "2_2") (pintype "input"))
      (node (ref "U7") (pin "1") (pinfunction "I/O_1_1") (pintype "bidirectional"))
    )
    (net (code "62") (name "USB_OTG_FS_ID") (class "Default")
      (node (ref "P5") (pin "4") (pinfunction "4_4") (pintype "input"))
      (node (ref "U1") (pin "1") (pinfunction "GPIO0(USB_HS_ID)_1") (pintype "bidirectional"))
    )
    (net (code "63") (name "USB_VBUS") (class "Default")
      (node (ref "P5") (pin "1") (pinfunction "1_1") (pintype "input"))
      (node (ref "U7") (pin "5") (pinfunction "VBUS_5") (pintype "bidirectional"))
    )
    (net (code "64") (name "VIN") (class "Default")
      (node (ref "P2") (pin "11") (pinfunction "11_11") (pintype "passive"))
      (node (ref "U1") (pin "39") (pinfunction "V_IN_39") (pintype "bidirectional"))
    )
    (net (code "65") (name "unconnected-(H1-MOUNT-PadB3,2)") (class "Default")
      (node (ref "H1") (pin "B3,2") (pinfunction "MOUNT_B3,2") (pintype "passive"))
    )
    (net (code "66") (name "unconnected-(H2-MOUNT-PadB3,2)") (class "Default")
      (node (ref "H2") (pin "B3,2") (pinfunction "MOUNT_B3,2") (pintype "passive"))
    )
    (net (code "67") (name "unconnected-(H3-MOUNT-PadB3,2)") (class "Default")
      (node (ref "H3") (pin "B3,2") (pinfunction "MOUNT_B3,2") (pintype "passive"))
    )
    (net (code "68") (name "unconnected-(H4-MOUNT-PadB3,2)") (class "Default")
      (node (ref "H4") (pin "B3,2") (pinfunction "MOUNT_B3,2") (pintype "passive"))
    )
    (net (code "69") (name "unconnected-(J1-NC1-Pad4)") (class "Default")
      (node (ref "J1") (pin "4") (pinfunction "NC1_4") (pintype "bidirectional"))
    )
    (net (code "70") (name "unconnected-(J1-NC2-Pad10)") (class "Default")
      (node (ref "J1") (pin "10") (pinfunction "NC2_10") (pintype "bidirectional"))
    )
    (net (code "71") (name "unconnected-(J2-NC1-Pad4)") (class "Default")
      (node (ref "J2") (pin "4") (pinfunction "NC1_4") (pintype "bidirectional"))
    )
    (net (code "72") (name "unconnected-(J2-NC2-Pad10)") (class "Default")
      (node (ref "J2") (pin "10") (pinfunction "NC2_10") (pintype "bidirectional"))
    )
    (net (code "73") (name "unconnected-(J3-NC1-Pad4)") (class "Default")
      (node (ref "J3") (pin "4") (pinfunction "NC1_4") (pintype "bidirectional"))
    )
    (net (code "74") (name "unconnected-(J3-NC2-Pad10)") (class "Default")
      (node (ref "J3") (pin "10") (pinfunction "NC2_10") (pintype "bidirectional"))
    )
    (net (code "75") (name "unconnected-(J4-NC1-Pad4)") (class "Default")
      (node (ref "J4") (pin "4") (pinfunction "NC1_4") (pintype "bidirectional"))
    )
    (net (code "76") (name "unconnected-(J4-NC2-Pad10)") (class "Default")
      (node (ref "J4") (pin "10") (pinfunction "NC2_10") (pintype "bidirectional"))
    )
    (net (code "77") (name "unconnected-(P1-A-PadSWA)") (class "Default")
      (node (ref "P1") (pin "SWA") (pinfunction "A_SWA") (pintype "bidirectional"))
    )
    (net (code "78") (name "unconnected-(P5-GND1-PadCASING1)") (class "Default")
      (node (ref "P5") (pin "CASING1") (pinfunction "GND1_CASING1") (pintype "bidirectional"))
    )
    (net (code "79") (name "unconnected-(P5-GND2-PadCASING2)") (class "Default")
      (node (ref "P5") (pin "CASING2") (pinfunction "GND2_CASING2") (pintype "bidirectional"))
    )
    (net (code "80") (name "unconnected-(P5-GND3-PadCASING3)") (class "Default")
      (node (ref "P5") (pin "CASING3") (pinfunction "GND3_CASING3") (pintype "bidirectional"))
    )
    (net (code "81") (name "unconnected-(P5-GND4-PadCASING4)") (class "Default")
      (node (ref "P5") (pin "CASING4") (pinfunction "GND4_CASING4") (pintype "bidirectional"))
    )
  )
)
